# 14_1ST_AP1302_ISP.net
KiCad netlist of a schematic drawn in Altium Designer
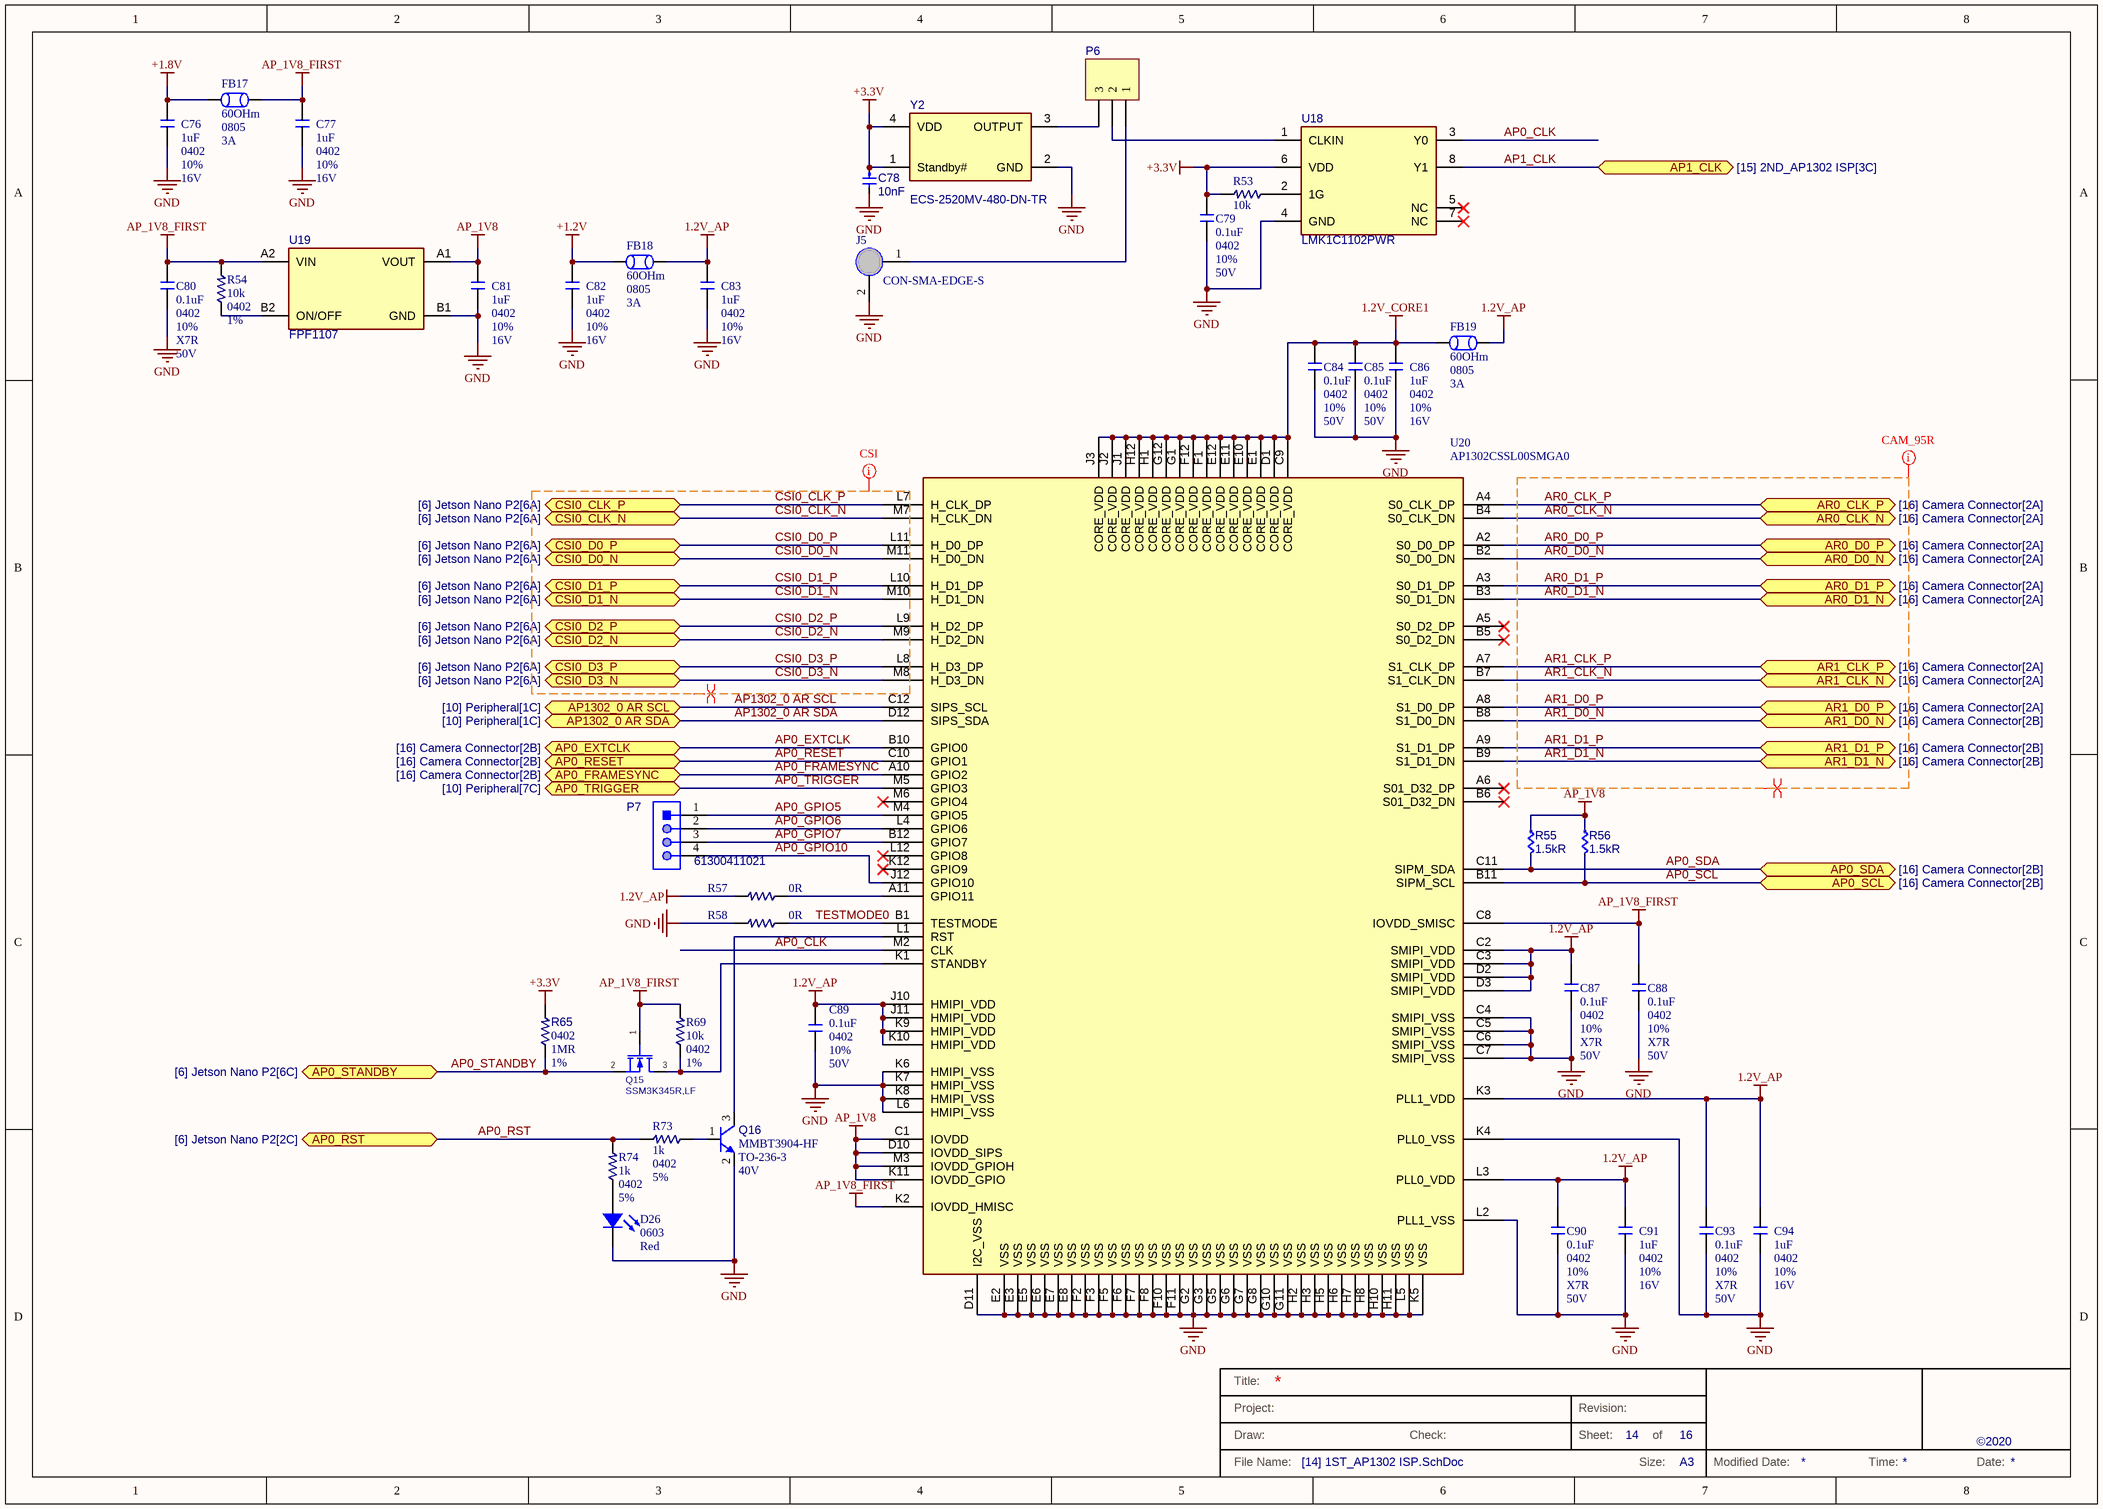
[diagram p0: [14] 1ST_AP1302 ISP.SchDoc]

(export (version "E")
  (design (tool "Eeschema 10.0.6"))
  (components
    (comp (ref "C76")
      (value "1uF")
      (footprint "C0402M")
      (fields
        (field (name "CASE CODE (IMPERIAL)") "0402")
        (field (name "TOLERANCE") "10%")
        (field (name "VOLTAGE") "16V")
      )
      (libsource (lib "CommonLib") (part "CAP_CER"))
    )
    (comp (ref "C77")
      (value "1uF")
      (footprint "C0402M")
      (fields
        (field (name "CASE CODE (IMPERIAL)") "0402")
        (field (name "TOLERANCE") "10%")
        (field (name "VOLTAGE") "16V")
      )
      (libsource (lib "CommonLib") (part "CAP_CER"))
    )
    (comp (ref "C78")
      (value "885012205050")
      (footprint "CAP0402-M")
      (description "CAP CER 10000PF 25V X7R 0402")
      (fields (field (name "TOLERANCE") "10%") (field (name "CAPACITANCE") "10nF"))
      (libsource (lib "Altium Central") (part "=Capacitance"))
    )
    (comp (ref "C79")
      (value "0.1uF")
      (footprint "C0402M")
      (description "CAP CER 0.1UF 50V X7R 0402")
      (fields
        (field (name "MANUFACTURER") "Murata")
        (field (name "MANUFACTURER PART NUMBER") "GRM155R71H104KE14D")
        (field (name "CASE/PACKAGE") "0402")
        (field (name "TOLERANCE") "10%")
        (field (name "VOLTAGE") "50V")
      )
      (libsource (lib "") (part "CAP_CER_1"))
    )
    (comp (ref "C80")
      (value "0.1uF")
      (footprint "C0402M")
      (description "CAP CER 0.1UF 50V X7R 0402")
      (fields
        (field (name "MANUFACTURER") "Murata")
        (field (name "MANUFACTURER PART NUMBER") "GRM155R71H104KE14D")
        (field (name "CASE/PACKAGE") "0402")
        (field (name "TOLERANCE") "10%")
        (field (name "DIELECTRIC") "X7R")
        (field (name "VOLTAGE") "50V")
      )
      (libsource (lib "") (part "CAP_CER_1"))
    )
    (comp (ref "C81")
      (value "1uF")
      (footprint "C0402M")
      (fields
        (field (name "CASE CODE (IMPERIAL)") "0402")
        (field (name "TOLERANCE") "10%")
        (field (name "VOLTAGE") "16V")
      )
      (libsource (lib "CommonLib") (part "CAP_CER"))
    )
    (comp (ref "C82")
      (value "1uF")
      (footprint "C0402M")
      (fields
        (field (name "CASE CODE (IMPERIAL)") "0402")
        (field (name "TOLERANCE") "10%")
        (field (name "VOLTAGE") "16V")
      )
      (libsource (lib "CommonLib") (part "CAP_CER"))
    )
    (comp (ref "C83")
      (value "1uF")
      (footprint "C0402M")
      (fields
        (field (name "CASE CODE (IMPERIAL)") "0402")
        (field (name "TOLERANCE") "10%")
        (field (name "VOLTAGE") "16V")
      )
      (libsource (lib "CommonLib") (part "CAP_CER"))
    )
    (comp (ref "C84")
      (value "0.1uF")
      (footprint "C0402M")
      (description "CAP CER 0.1UF 50V X7R 0402")
      (fields
        (field (name "MANUFACTURER") "Murata")
        (field (name "MANUFACTURER PART NUMBER") "GRM155R71H104KE14D")
        (field (name "CASE/PACKAGE") "0402")
        (field (name "TOLERANCE") "10%")
        (field (name "VOLTAGE") "50V")
      )
      (libsource (lib "") (part "CAP_CER_1"))
    )
    (comp (ref "C85")
      (value "0.1uF")
      (footprint "C0402M")
      (description "CAP CER 0.1UF 50V X7R 0402")
      (fields
        (field (name "MANUFACTURER") "Murata")
        (field (name "MANUFACTURER PART NUMBER") "GRM155R71H104KE14D")
        (field (name "CASE/PACKAGE") "0402")
        (field (name "TOLERANCE") "10%")
        (field (name "VOLTAGE") "50V")
      )
      (libsource (lib "") (part "CAP_CER_1"))
    )
    (comp (ref "C86")
      (value "1uF")
      (footprint "C0402M")
      (fields
        (field (name "CASE CODE (IMPERIAL)") "0402")
        (field (name "TOLERANCE") "10%")
        (field (name "VOLTAGE") "16V")
      )
      (libsource (lib "CommonLib") (part "CAP_CER"))
    )
    (comp (ref "C87")
      (value "0.1uF")
      (footprint "C0402M")
      (description "CAP CER 0.1UF 50V X7R 0402")
      (fields
        (field (name "MANUFACTURER") "Murata")
        (field (name "MANUFACTURER PART NUMBER") "GRM155R71H104KE14D")
        (field (name "CASE/PACKAGE") "0402")
        (field (name "TOLERANCE") "10%")
        (field (name "DIELECTRIC") "X7R")
        (field (name "VOLTAGE") "50V")
      )
      (libsource (lib "") (part "CAP_CER_1"))
    )
    (comp (ref "C88")
      (value "0.1uF")
      (footprint "C0402M")
      (description "CAP CER 0.1UF 50V X7R 0402")
      (fields
        (field (name "MANUFACTURER") "Murata")
        (field (name "MANUFACTURER PART NUMBER") "GRM155R71H104KE14D")
        (field (name "CASE/PACKAGE") "0402")
        (field (name "TOLERANCE") "10%")
        (field (name "DIELECTRIC") "X7R")
        (field (name "VOLTAGE") "50V")
      )
      (libsource (lib "") (part "CAP_CER_1"))
    )
    (comp (ref "C89")
      (value "0.1uF")
      (footprint "C0402M")
      (description "CAP CER 0.1UF 50V X7R 0402")
      (fields
        (field (name "MANUFACTURER") "Murata")
        (field (name "MANUFACTURER PART NUMBER") "GRM155R71H104KE14D")
        (field (name "CASE/PACKAGE") "0402")
        (field (name "TOLERANCE") "10%")
        (field (name "VOLTAGE") "50V")
      )
      (libsource (lib "") (part "CAP_CER_1"))
    )
    (comp (ref "C90")
      (value "0.1uF")
      (footprint "C0402M")
      (description "CAP CER 0.1UF 50V X7R 0402")
      (fields
        (field (name "MANUFACTURER") "Murata")
        (field (name "MANUFACTURER PART NUMBER") "GRM155R71H104KE14D")
        (field (name "CASE/PACKAGE") "0402")
        (field (name "TOLERANCE") "10%")
        (field (name "DIELECTRIC") "X7R")
        (field (name "VOLTAGE") "50V")
      )
      (libsource (lib "") (part "CAP_CER_1"))
    )
    (comp (ref "C91")
      (value "1uF")
      (footprint "C0402M")
      (fields
        (field (name "CASE CODE (IMPERIAL)") "0402")
        (field (name "TOLERANCE") "10%")
        (field (name "VOLTAGE") "16V")
      )
      (libsource (lib "CommonLib") (part "CAP_CER"))
    )
    (comp (ref "C93")
      (value "0.1uF")
      (footprint "C0402M")
      (description "CAP CER 0.1UF 50V X7R 0402")
      (fields
        (field (name "MANUFACTURER") "Murata")
        (field (name "MANUFACTURER PART NUMBER") "GRM155R71H104KE14D")
        (field (name "CASE/PACKAGE") "0402")
        (field (name "TOLERANCE") "10%")
        (field (name "DIELECTRIC") "X7R")
        (field (name "VOLTAGE") "50V")
      )
      (libsource (lib "") (part "CAP_CER_1"))
    )
    (comp (ref "C94")
      (value "1uF")
      (footprint "C0402M")
      (fields
        (field (name "CASE CODE (IMPERIAL)") "0402")
        (field (name "TOLERANCE") "10%")
        (field (name "VOLTAGE") "16V")
      )
      (libsource (lib "CommonLib") (part "CAP_CER"))
    )
    (comp (ref "D26")
      (value "LTST-C190CKT")
      (footprint "LED-0603")
      (description "LED RED CLEAR CHIP SMD")
      (fields (field (name "CASE/PACKAGE") "0603") (field (name "COLOR") "Red"))
      (libsource (lib "CommonLib") (part "Led"))
    )
    (comp (ref "FB17")
      (value "60OHm")
      (footprint "R0805M")
      (fields
        (field (name "CASE CODE (IMPERIAL)") "0805")
        (field (name "TOLERANCE") "25%")
        (field (name "MAX DC CURRENT") "3A")
      )
      (libsource (lib "CommonLib") (part "FB"))
    )
    (comp (ref "FB18")
      (value "60OHm")
      (footprint "R0805M")
      (fields
        (field (name "CASE CODE (IMPERIAL)") "0805")
        (field (name "TOLERANCE") "25%")
        (field (name "MAX DC CURRENT") "3A")
      )
      (libsource (lib "CommonLib") (part "FB"))
    )
    (comp (ref "FB19")
      (value "60OHm")
      (footprint "R0805M")
      (fields
        (field (name "CASE CODE (IMPERIAL)") "0805")
        (field (name "TOLERANCE") "25%")
        (field (name "MAX DC CURRENT") "3A")
      )
      (libsource (lib "CommonLib") (part "FB"))
    )
    (comp (ref "J5")
      (value "CON-SMA-EDGE-S")
      (footprint "CON-SMA-EDGE-S")
      (description "Sma Female Connector, Pcb Edge Mount Rohs Compliant: Yes")
      (libsource (lib "CommonLib") (part "AntenaIPX"))
    )
    (comp (ref "P6")
      (value "Header 3")
      (footprint "HDR1X3")
      (description "Header, 3-Pin")
      (fields (field (name "PUBLISHER") "Altium Limited"))
      (libsource (lib "3DAS_4Camera") (part "Header 3"))
    )
    (comp (ref "P7")
      (value "61300411021")
      (footprint "61300411021")
      (description "CONN HEADER VERT 4POS 2.54MM")
      (fields (field (name "MANUFACTURER") "Würth Elektronik GmbH"))
      (libsource (lib "3DAS_4Camera") (part "WE-CN-1P-M-R4"))
    )
    (comp (ref "Q15")
      (value "SSM3K345R,LF")
      (footprint "SSM3K345R,LF-Footprint-1")
      (description "MOSFET N-CHANNEL 20V 4A SOT23F")
      (libsource (lib "Altium Central") (part "SSM3K345R,LF"))
    )
    (comp (ref "Q16")
      (value "NPN")
      (footprint "SOT55P160X90-3N")
      (description "TRANS NPN 40V 0.2A SOT523")
      (fields
        (field (name "MANUFACTURER PART NUMBER 1") "MMBT3904-HF")
        (field (name "CASE/PACKAGE") "TO-236-3")
        (field (name "COLLECTOR EMITTER BREAKDOWN VOLTAGE") "40V")
      )
      (libsource (lib "3DAS_4Camera") (part "NPN"))
    )
    (comp (ref "R53")
      (value "10k")
      (footprint "R0402M")
      (description "RES SMD 10K OHM 1% 1/16W 0402")
      (fields
        (field (name "MANUFACTURER") "Yageo")
        (field (name "MANUFACTURER PART NUMBER") "RC0402FR-0710KL")
      )
      (libsource (lib "CommonLib") (part "RES_SMD"))
    )
    (comp (ref "R54")
      (value "10k")
      (footprint "R0402M")
      (description "RES SMD 10K OHM 1% 1/16W 0402")
      (fields
        (field (name "MANUFACTURER") "Yageo")
        (field (name "MANUFACTURER PART NUMBER") "RC0402FR-0710KL")
        (field (name "CASE CODE (IMPERIAL)") "0402")
        (field (name "TOLERANCE") "1%")
      )
      (libsource (lib "CommonLib") (part "RES_SMD"))
    )
    (comp (ref "R55")
      (value "ERJ-2RKF1501X")
      (footprint "RES0402")
      (description "RES SMD 1.5K OHM 1% 1/10W 0402")
      (fields (field (name "RESISTANCE") "1.5kR") (field (name "TOLERANCE") "1%"))
      (libsource (lib "Altium Central") (part "=Resistance"))
    )
    (comp (ref "R56")
      (value "ERJ-2RKF1501X")
      (footprint "RES0402")
      (description "RES SMD 1.5K OHM 1% 1/10W 0402")
      (fields (field (name "RESISTANCE") "1.5kR") (field (name "TOLERANCE") "1%"))
      (libsource (lib "Altium Central") (part "=Resistance"))
    )
    (comp (ref "R57")
      (value "RC0402FR-070RL")
      (footprint "R0402M")
      (description "RC Series 0402 0.063 W 0 Ohm Jumper Surface Mount Thick Film Chip Resistor")
      (fields (field (name "RESISTANCE") "0R") (field (name "TOLERANCE") "1%"))
      (libsource (lib "CommonLib") (part "RES_SMD"))
    )
    (comp (ref "R58")
      (value "RC0402FR-070RL")
      (footprint "R0402M")
      (description "RC Series 0402 0.063 W 0 Ohm Jumper Surface Mount Thick Film Chip Resistor")
      (fields (field (name "RESISTANCE") "0R") (field (name "TOLERANCE") "1%"))
      (libsource (lib "CommonLib") (part "RES_SMD"))
    )
    (comp (ref "R65")
      (value "1M")
      (footprint "R0402M")
      (description "RES SMD 1M OHM 1% 1/16W 0402")
      (fields
        (field (name "MANUFACTURER") "Yageo")
        (field (name "MANUFACTURER PART NUMBER") "RC0402FR-071ML")
        (field (name "CASE CODE (IMPERIAL)") "0402")
        (field (name "RESISTANCE") "1MR")
        (field (name "TOLERANCE") "1%")
      )
      (libsource (lib "3DAS_4Camera") (part "RES_SMD_17"))
    )
    (comp (ref "R69")
      (value "10k")
      (footprint "R0402M")
      (description "RES SMD 10K OHM 1% 1/16W 0402")
      (fields
        (field (name "MANUFACTURER") "Yageo")
        (field (name "MANUFACTURER PART NUMBER") "RC0402FR-0710KL")
        (field (name "CASE CODE (IMPERIAL)") "0402")
        (field (name "TOLERANCE") "1%")
      )
      (libsource (lib "CommonLib") (part "RES_SMD"))
    )
    (comp (ref "R73")
      (value "1k")
      (footprint "R0402M")
      (description "RES SMD 1K OHM 5% 1/16W 0402")
      (fields
        (field (name "MANUFACTURER") "Yageo")
        (field (name "MANUFACTURER PART NUMBER") "RC0402JR-071KL")
        (field (name "CASE CODE (IMPERIAL)") "0402")
        (field (name "TOLERANCE") "5%")
      )
      (libsource (lib "CommonLib") (part "RES_SMD"))
    )
    (comp (ref "R74")
      (value "1k")
      (footprint "R0402M")
      (description "RES SMD 1K OHM 5% 1/16W 0402")
      (fields
        (field (name "MANUFACTURER") "Yageo")
        (field (name "MANUFACTURER PART NUMBER") "RC0402JR-071KL")
        (field (name "CASE CODE (IMPERIAL)") "0402")
        (field (name "TOLERANCE") "5%")
      )
      (libsource (lib "CommonLib") (part "RES_SMD"))
    )
    (comp (ref "U18")
      (value "LMK1C1102PWR")
      (footprint "LMK1C1102PWR")
      (description "Clock Buffer LVCMOS 1: 4 1.8V/2.5V/3.3V 8-Pin TSSOP T/R")
      (fields (field (name "MANUFACTURER") "Texas Instruments"))
      (libsource (lib "3DAS_4Camera") (part "LMK1C1102PWR"))
    )
    (comp (ref "U19")
      (value "FPF1107")
      (footprint "FPF1107")
      (description "IC PWR SWITCH P-CHAN 1:1 4WLCSP")
      (fields (field (name "MANUFACTURER") "ON Semiconductor / Fairchild") (field (name "VOLTAGE") "4V"))
      (libsource (lib "3DAS_4Camera") (part "FPF1107"))
    )
    (comp (ref "U20")
      (value "AP1302CSSL00SMGA0")
      (footprint "AP1302CSSL00SMGA0")
      (description "IMAGE SENSOR 13 MP CO-PROCESSOR")
      (fields
        (field (name "MANUFACTURER") "ON Semiconductor")
        (field (name "MANUFACTURER PART NUMBER") "AP1302CSSL00SMGA0-DR")
      )
      (libsource (lib "3DAS_4Camera") (part "AP1302"))
    )
    (comp (ref "Y2")
      (value "ECS-2520MV-480-DN-TR")
      (footprint "ECS-2520MV-480-DN-TR")
      (description "XTAL OSC XO 48.0000MHZ CMOS SMD")
      (fields
        (field (name "MANUFACTURER") "ECS International")
        (field (name "MANUFACTURER PART NUMBER") "ECS-2520MV-480-DN-TR")
      )
      (libsource (lib "3DAS_4Camera") (part "ASFLMB-48.000MHZ-LR-T"))
    )
  )
  (nets
    (net (code "1") (name "+1.2V") (class "Default")
      (node (ref "C82") (pin "1") (pinfunction "1_1") (pintype "passive"))
      (node (ref "FB18") (pin "2") (pinfunction "2_2") (pintype "passive"))
    )
    (net (code "2") (name "+1.8V") (class "Default")
      (node (ref "C76") (pin "1") (pinfunction "1_1") (pintype "passive"))
      (node (ref "FB17") (pin "2") (pinfunction "2_2") (pintype "passive"))
    )
    (net (code "3") (name "+3.3V") (class "Default")
      (node (ref "C78") (pin "1") (pinfunction "1_1") (pintype "passive"))
      (node (ref "C79") (pin "1") (pinfunction "1_1") (pintype "passive"))
      (node (ref "R53") (pin "1") (pinfunction "1_1") (pintype "passive"))
      (node (ref "R65") (pin "1") (pinfunction "1_1") (pintype "passive"))
      (node (ref "U18") (pin "6") (pinfunction "VDD_6") (pintype "passive"))
      (node (ref "Y2") (pin "1") (pinfunction "Standby#_1") (pintype "passive"))
      (node (ref "Y2") (pin "4") (pinfunction "VDD_4") (pintype "passive"))
    )
    (net (code "4") (name "/AP0_CLK") (class "Default")
      (node (ref "U18") (pin "3") (pinfunction "Y0_3") (pintype "passive"))
      (node (ref "U20") (pin "M2") (pinfunction "CLK_M2") (pintype "passive"))
    )
    (net (code "5") (name "/AP0_EXTCLK") (class "Default")
      (node (ref "U20") (pin "B10") (pinfunction "GPIO0_B10") (pintype "passive"))
    )
    (net (code "6") (name "/AP0_FRAMESYNC") (class "Default")
      (node (ref "U20") (pin "A10") (pinfunction "GPIO2_A10") (pintype "passive"))
    )
    (net (code "7") (name "/AP0_GPIO5") (class "Default")
      (node (ref "P7") (pin "1") (pinfunction "1_1") (pintype "passive"))
      (node (ref "U20") (pin "M4") (pinfunction "GPIO5_M4") (pintype "passive"))
    )
    (net (code "8") (name "/AP0_GPIO6") (class "Default")
      (node (ref "P7") (pin "2") (pinfunction "2_2") (pintype "passive"))
      (node (ref "U20") (pin "L4") (pinfunction "GPIO6_L4") (pintype "passive"))
    )
    (net (code "9") (name "/AP0_GPIO7") (class "Default")
      (node (ref "P7") (pin "3") (pinfunction "3_3") (pintype "passive"))
      (node (ref "U20") (pin "B12") (pinfunction "GPIO7_B12") (pintype "passive"))
    )
    (net (code "10") (name "/AP0_GPIO10") (class "Default")
      (node (ref "P7") (pin "4") (pinfunction "4_4") (pintype "passive"))
      (node (ref "U20") (pin "J12") (pinfunction "GPIO10_J12") (pintype "passive"))
    )
    (net (code "11") (name "/AP0_RESET") (class "Default")
      (node (ref "U20") (pin "C10") (pinfunction "GPIO1_C10") (pintype "passive"))
    )
    (net (code "12") (name "/AP0_RST") (class "Default")
      (node (ref "R73") (pin "1") (pinfunction "1_1") (pintype "passive"))
      (node (ref "R74") (pin "1") (pinfunction "1_1") (pintype "passive"))
    )
    (net (code "13") (name "/AP0_SCL") (class "Default")
      (node (ref "R56") (pin "2") (pinfunction "2_2") (pintype "passive"))
      (node (ref "U20") (pin "B11") (pinfunction "SIPM_SCL_B11") (pintype "passive"))
    )
    (net (code "14") (name "/AP0_SDA") (class "Default")
      (node (ref "R55") (pin "2") (pinfunction "2_2") (pintype "passive"))
      (node (ref "U20") (pin "C11") (pinfunction "SIPM_SDA_C11") (pintype "passive"))
    )
    (net (code "15") (name "/AP0_STANDBY") (class "Default")
      (node (ref "Q15") (pin "2") (pinfunction "S_2") (pintype "passive"))
      (node (ref "R65") (pin "2") (pinfunction "2_2") (pintype "passive"))
    )
    (net (code "16") (name "/AP0_TRIGGER") (class "Default")
      (node (ref "U20") (pin "M5") (pinfunction "GPIO3_M5") (pintype "passive"))
    )
    (net (code "17") (name "/AP1_CLK") (class "Default")
      (node (ref "U18") (pin "8") (pinfunction "Y1_8") (pintype "passive"))
    )
    (net (code "18") (name "/AP1302_0 AR SCL") (class "Default")
      (node (ref "U20") (pin "C12") (pinfunction "SIPS_SCL_C12") (pintype "passive"))
    )
    (net (code "19") (name "/AP1302_0 AR SDA") (class "Default")
      (node (ref "U20") (pin "D12") (pinfunction "SIPS_SDA_D12") (pintype "passive"))
    )
    (net (code "20") (name "/AR0_CLK_N") (class "Default")
      (node (ref "U20") (pin "B4") (pinfunction "S0_CLK_DN_B4") (pintype "passive"))
    )
    (net (code "21") (name "/AR0_CLK_P") (class "Default")
      (node (ref "U20") (pin "A4") (pinfunction "S0_CLK_DP_A4") (pintype "passive"))
    )
    (net (code "22") (name "/AR0_D0_N") (class "Default")
      (node (ref "U20") (pin "B2") (pinfunction "S0_D0_DN_B2") (pintype "passive"))
    )
    (net (code "23") (name "/AR0_D0_P") (class "Default")
      (node (ref "U20") (pin "A2") (pinfunction "S0_D0_DP_A2") (pintype "passive"))
    )
    (net (code "24") (name "/AR0_D1_N") (class "Default")
      (node (ref "U20") (pin "B3") (pinfunction "S0_D1_DN_B3") (pintype "passive"))
    )
    (net (code "25") (name "/AR0_D1_P") (class "Default")
      (node (ref "U20") (pin "A3") (pinfunction "S0_D1_DP_A3") (pintype "passive"))
    )
    (net (code "26") (name "/AR1_CLK_N") (class "Default")
      (node (ref "U20") (pin "B7") (pinfunction "S1_CLK_DN_B7") (pintype "passive"))
    )
    (net (code "27") (name "/AR1_CLK_P") (class "Default")
      (node (ref "U20") (pin "A7") (pinfunction "S1_CLK_DP_A7") (pintype "passive"))
    )
    (net (code "28") (name "/AR1_D0_N") (class "Default")
      (node (ref "U20") (pin "B8") (pinfunction "S1_D0_DN_B8") (pintype "passive"))
    )
    (net (code "29") (name "/AR1_D0_P") (class "Default")
      (node (ref "U20") (pin "A8") (pinfunction "S1_D0_DP_A8") (pintype "passive"))
    )
    (net (code "30") (name "/AR1_D1_N") (class "Default")
      (node (ref "U20") (pin "B9") (pinfunction "S1_D1_DN_B9") (pintype "passive"))
    )
    (net (code "31") (name "/AR1_D1_P") (class "Default")
      (node (ref "U20") (pin "A9") (pinfunction "S1_D1_DP_A9") (pintype "passive"))
    )
    (net (code "32") (name "/CSI0_CLK_N") (class "Default")
      (node (ref "U20") (pin "M7") (pinfunction "H_CLK_DN_M7") (pintype "passive"))
    )
    (net (code "33") (name "/CSI0_CLK_P") (class "Default")
      (node (ref "U20") (pin "L7") (pinfunction "H_CLK_DP_L7") (pintype "passive"))
    )
    (net (code "34") (name "/CSI0_D0_N") (class "Default")
      (node (ref "U20") (pin "M11") (pinfunction "H_D0_DN_M11") (pintype "passive"))
    )
    (net (code "35") (name "/CSI0_D0_P") (class "Default")
      (node (ref "U20") (pin "L11") (pinfunction "H_D0_DP_L11") (pintype "passive"))
    )
    (net (code "36") (name "/CSI0_D1_N") (class "Default")
      (node (ref "U20") (pin "M10") (pinfunction "H_D1_DN_M10") (pintype "passive"))
    )
    (net (code "37") (name "/CSI0_D1_P") (class "Default")
      (node (ref "U20") (pin "L10") (pinfunction "H_D1_DP_L10") (pintype "passive"))
    )
    (net (code "38") (name "/CSI0_D2_N") (class "Default")
      (node (ref "U20") (pin "M9") (pinfunction "H_D2_DN_M9") (pintype "passive"))
    )
    (net (code "39") (name "/CSI0_D2_P") (class "Default")
      (node (ref "U20") (pin "L9") (pinfunction "H_D2_DP_L9") (pintype "passive"))
    )
    (net (code "40") (name "/CSI0_D3_N") (class "Default")
      (node (ref "U20") (pin "M8") (pinfunction "H_D3_DN_M8") (pintype "passive"))
    )
    (net (code "41") (name "/CSI0_D3_P") (class "Default")
      (node (ref "U20") (pin "L8") (pinfunction "H_D3_DP_L8") (pintype "passive"))
    )
    (net (code "42") (name "/TESTMODE0") (class "Default")
      (node (ref "R58") (pin "2") (pinfunction "2_2") (pintype "passive"))
      (node (ref "U20") (pin "B1") (pinfunction "TESTMODE_B1") (pintype "passive"))
    )
    (net (code "43") (name "1.2V_AP") (class "Default")
      (node (ref "C83") (pin "1") (pinfunction "1_1") (pintype "passive"))
      (node (ref "C87") (pin "1") (pinfunction "1_1") (pintype "passive"))
      (node (ref "C89") (pin "1") (pinfunction "1_1") (pintype "passive"))
      (node (ref "C90") (pin "1") (pinfunction "1_1") (pintype "passive"))
      (node (ref "C91") (pin "1") (pinfunction "1_1") (pintype "passive"))
      (node (ref "C93") (pin "1") (pinfunction "1_1") (pintype "passive"))
      (node (ref "C94") (pin "1") (pinfunction "1_1") (pintype "passive"))
      (node (ref "FB18") (pin "1") (pinfunction "1_1") (pintype "passive"))
      (node (ref "FB19") (pin "1") (pinfunction "1_1") (pintype "passive"))
      (node (ref "R57") (pin "1") (pinfunction "1_1") (pintype "passive"))
      (node (ref "U20") (pin "C2") (pinfunction "SMIPI_VDD_C2") (pintype "passive"))
      (node (ref "U20") (pin "C3") (pinfunction "SMIPI_VDD_C3") (pintype "passive"))
      (node (ref "U20") (pin "D2") (pinfunction "SMIPI_VDD_D2") (pintype "passive"))
      (node (ref "U20") (pin "D3") (pinfunction "SMIPI_VDD_D3") (pintype "passive"))
      (node (ref "U20") (pin "J10") (pinfunction "HMIPI_VDD_J10") (pintype "passive"))
      (node (ref "U20") (pin "J11") (pinfunction "HMIPI_VDD_J11") (pintype "passive"))
      (node (ref "U20") (pin "K10") (pinfunction "HMIPI_VDD_K10") (pintype "passive"))
      (node (ref "U20") (pin "K3") (pinfunction "PLL1_VDD_K3") (pintype "passive"))
      (node (ref "U20") (pin "K9") (pinfunction "HMIPI_VDD_K9") (pintype "passive"))
      (node (ref "U20") (pin "L3") (pinfunction "PLL0_VDD_L3") (pintype "passive"))
    )
    (net (code "44") (name "1.2V_CORE1") (class "Default")
      (node (ref "C84") (pin "1") (pinfunction "1_1") (pintype "passive"))
      (node (ref "C85") (pin "1") (pinfunction "1_1") (pintype "passive"))
      (node (ref "C86") (pin "1") (pinfunction "1_1") (pintype "passive"))
      (node (ref "FB19") (pin "2") (pinfunction "2_2") (pintype "passive"))
      (node (ref "U20") (pin "C9") (pinfunction "CORE_VDD_C9") (pintype "passive"))
      (node (ref "U20") (pin "D1") (pinfunction "CORE_VDD_D1") (pintype "passive"))
      (node (ref "U20") (pin "E1") (pinfunction "CORE_VDD_E1") (pintype "passive"))
      (node (ref "U20") (pin "E10") (pinfunction "CORE_VDD_E10") (pintype "passive"))
      (node (ref "U20") (pin "E11") (pinfunction "CORE_VDD_E11") (pintype "passive"))
      (node (ref "U20") (pin "E12") (pinfunction "CORE_VDD_E12") (pintype "passive"))
      (node (ref "U20") (pin "F1") (pinfunction "CORE_VDD_F1") (pintype "passive"))
      (node (ref "U20") (pin "F12") (pinfunction "CORE_VDD_F12") (pintype "passive"))
      (node (ref "U20") (pin "G1") (pinfunction "CORE_VDD_G1") (pintype "passive"))
      (node (ref "U20") (pin "G12") (pinfunction "CORE_VDD_G12") (pintype "passive"))
      (node (ref "U20") (pin "H1") (pinfunction "CORE_VDD_H1") (pintype "passive"))
      (node (ref "U20") (pin "H12") (pinfunction "CORE_VDD_H12") (pintype "passive"))
      (node (ref "U20") (pin "J1") (pinfunction "CORE_VDD_J1") (pintype "passive"))
      (node (ref "U20") (pin "J2") (pinfunction "CORE_VDD_J2") (pintype "passive"))
      (node (ref "U20") (pin "J3") (pinfunction "CORE_VDD_J3") (pintype "passive"))
    )
    (net (code "45") (name "AP_1V8") (class "Default")
      (node (ref "C81") (pin "1") (pinfunction "1_1") (pintype "passive"))
      (node (ref "R55") (pin "1") (pinfunction "1_1") (pintype "passive"))
      (node (ref "R56") (pin "1") (pinfunction "1_1") (pintype "passive"))
      (node (ref "U19") (pin "A1") (pinfunction "VOUT_A1") (pintype "passive"))
      (node (ref "U20") (pin "C1") (pinfunction "IOVDD_C1") (pintype "passive"))
      (node (ref "U20") (pin "D10") (pinfunction "IOVDD_SIPS_D10") (pintype "passive"))
      (node (ref "U20") (pin "K11") (pinfunction "IOVDD_GPIO_K11") (pintype "passive"))
      (node (ref "U20") (pin "M3") (pinfunction "IOVDD_GPIOH_M3") (pintype "passive"))
    )
    (net (code "46") (name "AP_1V8_FIRST") (class "Default")
      (node (ref "C77") (pin "1") (pinfunction "1_1") (pintype "passive"))
      (node (ref "C80") (pin "1") (pinfunction "1_1") (pintype "passive"))
      (node (ref "C88") (pin "1") (pinfunction "1_1") (pintype "passive"))
      (node (ref "FB17") (pin "1") (pinfunction "1_1") (pintype "passive"))
      (node (ref "Q15") (pin "1") (pinfunction "G_1") (pintype "passive"))
      (node (ref "R54") (pin "1") (pinfunction "1_1") (pintype "passive"))
      (node (ref "R69") (pin "1") (pinfunction "1_1") (pintype "passive"))
      (node (ref "U19") (pin "A2") (pinfunction "VIN_A2") (pintype "passive"))
      (node (ref "U20") (pin "C8") (pinfunction "IOVDD_SMISC_C8") (pintype "passive"))
      (node (ref "U20") (pin "K2") (pinfunction "IOVDD_HMISC_K2") (pintype "passive"))
    )
    (net (code "47") (name "GND") (class "Default")
      (node (ref "C76") (pin "2") (pinfunction "2_2") (pintype "passive"))
      (node (ref "C77") (pin "2") (pinfunction "2_2") (pintype "passive"))
      (node (ref "C78") (pin "2") (pinfunction "2_2") (pintype "passive"))
      (node (ref "C79") (pin "2") (pinfunction "2_2") (pintype "passive"))
      (node (ref "C80") (pin "2") (pinfunction "2_2") (pintype "passive"))
      (node (ref "C81") (pin "2") (pinfunction "2_2") (pintype "passive"))
      (node (ref "C82") (pin "2") (pinfunction "2_2") (pintype "passive"))
      (node (ref "C83") (pin "2") (pinfunction "2_2") (pintype "passive"))
      (node (ref "C84") (pin "2") (pinfunction "2_2") (pintype "passive"))
      (node (ref "C85") (pin "2") (pinfunction "2_2") (pintype "passive"))
      (node (ref "C86") (pin "2") (pinfunction "2_2") (pintype "passive"))
      (node (ref "C87") (pin "2") (pinfunction "2_2") (pintype "passive"))
      (node (ref "C88") (pin "2") (pinfunction "2_2") (pintype "passive"))
      (node (ref "C89") (pin "2") (pinfunction "2_2") (pintype "passive"))
      (node (ref "C90") (pin "2") (pinfunction "2_2") (pintype "passive"))
      (node (ref "C91") (pin "2") (pinfunction "2_2") (pintype "passive"))
      (node (ref "C93") (pin "2") (pinfunction "2_2") (pintype "passive"))
      (node (ref "C94") (pin "2") (pinfunction "2_2") (pintype "passive"))
      (node (ref "D26") (pin "2") (pinfunction "K_2") (pintype "passive"))
      (node (ref "J5") (pin "2") (pinfunction "GND_2") (pintype "passive"))
      (node (ref "Q16") (pin "2") (pinfunction "E_2") (pintype "passive"))
      (node (ref "R58") (pin "1") (pinfunction "1_1") (pintype "passive"))
      (node (ref "U18") (pin "4") (pinfunction "GND_4") (pintype "passive"))
      (node (ref "U19") (pin "B1") (pinfunction "GND_B1") (pintype "passive"))
      (node (ref "U20") (pin "C4") (pinfunction "SMIPI_VSS_C4") (pintype "passive"))
      (node (ref "U20") (pin "C5") (pinfunction "SMIPI_VSS_C5") (pintype "passive"))
      (node (ref "U20") (pin "C6") (pinfunction "SMIPI_VSS_C6") (pintype "passive"))
      (node (ref "U20") (pin "C7") (pinfunction "SMIPI_VSS_C7") (pintype "passive"))
      (node (ref "U20") (pin "D11") (pinfunction "I2C_VSS_D11") (pintype "passive"))
      (node (ref "U20") (pin "E2") (pinfunction "VSS_E2") (pintype "passive"))
      (node (ref "U20") (pin "E3") (pinfunction "VSS_E3") (pintype "passive"))
      (node (ref "U20") (pin "E5") (pinfunction "VSS_E5") (pintype "passive"))
      (node (ref "U20") (pin "E6") (pinfunction "VSS_E6") (pintype "passive"))
      (node (ref "U20") (pin "E7") (pinfunction "VSS_E7") (pintype "passive"))
      (node (ref "U20") (pin "E8") (pinfunction "VSS_E8") (pintype "passive"))
      (node (ref "U20") (pin "F10") (pinfunction "VSS_F10") (pintype "passive"))
      (node (ref "U20") (pin "F11") (pinfunction "VSS_F11") (pintype "passive"))
      (node (ref "U20") (pin "F2") (pinfunction "VSS_F2") (pintype "passive"))
      (node (ref "U20") (pin "F3") (pinfunction "VSS_F3") (pintype "passive"))
      (node (ref "U20") (pin "F5") (pinfunction "VSS_F5") (pintype "passive"))
      (node (ref "U20") (pin "F6") (pinfunction "VSS_F6") (pintype "passive"))
      (node (ref "U20") (pin "F7") (pinfunction "VSS_F7") (pintype "passive"))
      (node (ref "U20") (pin "F8") (pinfunction "VSS_F8") (pintype "passive"))
      (node (ref "U20") (pin "G10") (pinfunction "VSS_G10") (pintype "passive"))
      (node (ref "U20") (pin "G11") (pinfunction "VSS_G11") (pintype "passive"))
      (node (ref "U20") (pin "G2") (pinfunction "VSS_G2") (pintype "passive"))
      (node (ref "U20") (pin "G3") (pinfunction "VSS_G3") (pintype "passive"))
      (node (ref "U20") (pin "G5") (pinfunction "VSS_G5") (pintype "passive"))
      (node (ref "U20") (pin "G6") (pinfunction "VSS_G6") (pintype "passive"))
      (node (ref "U20") (pin "G7") (pinfunction "VSS_G7") (pintype "passive"))
      (node (ref "U20") (pin "G8") (pinfunction "VSS_G8") (pintype "passive"))
      (node (ref "U20") (pin "H10") (pinfunction "VSS_H10") (pintype "passive"))
      (node (ref "U20") (pin "H11") (pinfunction "VSS_H11") (pintype "passive"))
      (node (ref "U20") (pin "H2") (pinfunction "VSS_H2") (pintype "passive"))
      (node (ref "U20") (pin "H3") (pinfunction "VSS_H3") (pintype "passive"))
      (node (ref "U20") (pin "H5") (pinfunction "VSS_H5") (pintype "passive"))
      (node (ref "U20") (pin "H6") (pinfunction "VSS_H6") (pintype "passive"))
      (node (ref "U20") (pin "H7") (pinfunction "VSS_H7") (pintype "passive"))
      (node (ref "U20") (pin "H8") (pinfunction "VSS_H8") (pintype "passive"))
      (node (ref "U20") (pin "K4") (pinfunction "PLL0_VSS_K4") (pintype "passive"))
      (node (ref "U20") (pin "K5") (pinfunction "VSS_K5") (pintype "passive"))
      (node (ref "U20") (pin "K6") (pinfunction "HMIPI_VSS_K6") (pintype "passive"))
      (node (ref "U20") (pin "K7") (pinfunction "HMIPI_VSS_K7") (pintype "passive"))
      (node (ref "U20") (pin "K8") (pinfunction "HMIPI_VSS_K8") (pintype "passive"))
      (node (ref "U20") (pin "L2") (pinfunction "PLL1_VSS_L2") (pintype "passive"))
      (node (ref "U20") (pin "L5") (pinfunction "VSS_L5") (pintype "passive"))
      (node (ref "U20") (pin "L6") (pinfunction "HMIPI_VSS_L6") (pintype "passive"))
      (node (ref "Y2") (pin "2") (pinfunction "GND_2") (pintype "passive"))
    )
    (net (code "48") (name "Net-(D26-A)") (class "Default")
      (node (ref "D26") (pin "1") (pinfunction "A_1") (pintype "passive"))
      (node (ref "R74") (pin "2") (pinfunction "2_2") (pintype "passive"))
    )
    (net (code "49") (name "Net-(J5-SIG)") (class "Default")
      (node (ref "J5") (pin "1") (pinfunction "SIG_1") (pintype "passive"))
      (node (ref "P6") (pin "1") (pinfunction "1_1") (pintype "passive"))
    )
    (net (code "50") (name "Net-(Q15-D)") (class "Default")
      (node (ref "Q15") (pin "3") (pinfunction "D_3") (pintype "passive"))
      (node (ref "R69") (pin "2") (pinfunction "2_2") (pintype "passive"))
      (node (ref "U20") (pin "K1") (pinfunction "STANDBY_K1") (pintype "passive"))
    )
    (net (code "51") (name "Net-(Q16-B)") (class "Default")
      (node (ref "Q16") (pin "1") (pinfunction "B_1") (pintype "passive"))
      (node (ref "R73") (pin "2") (pinfunction "2_2") (pintype "passive"))
    )
    (net (code "52") (name "Net-(Q16-C)") (class "Default")
      (node (ref "Q16") (pin "3") (pinfunction "C_3") (pintype "passive"))
      (node (ref "U20") (pin "L1") (pinfunction "RST_L1") (pintype "passive"))
    )
    (net (code "53") (name "Net-(U18-1G)") (class "Default")
      (node (ref "R53") (pin "2") (pinfunction "2_2") (pintype "passive"))
      (node (ref "U18") (pin "2") (pinfunction "1G_2") (pintype "passive"))
    )
    (net (code "54") (name "Net-(U18-CLKIN)") (class "Default")
      (node (ref "P6") (pin "2") (pinfunction "2_2") (pintype "passive"))
      (node (ref "U18") (pin "1") (pinfunction "CLKIN_1") (pintype "passive"))
    )
    (net (code "55") (name "Net-(U19-ON{slash}OFF)") (class "Default")
      (node (ref "R54") (pin "2") (pinfunction "2_2") (pintype "passive"))
      (node (ref "U19") (pin "B2") (pinfunction "ON/OFF_B2") (pintype "passive"))
    )
    (net (code "56") (name "Net-(U20-GPIO11)") (class "Default")
      (node (ref "R57") (pin "2") (pinfunction "2_2") (pintype "passive"))
      (node (ref "U20") (pin "A11") (pinfunction "GPIO11_A11") (pintype "passive"))
    )
    (net (code "57") (name "Net-(Y2-OUTPUT)") (class "Default")
      (node (ref "P6") (pin "3") (pinfunction "3_3") (pintype "passive"))
      (node (ref "Y2") (pin "3") (pinfunction "OUTPUT_3") (pintype "passive"))
    )
    (net (code "58") (name "unconnected-(U18-NC-Pad5)") (class "Default")
      (node (ref "U18") (pin "5") (pinfunction "NC_5") (pintype "passive+no_connect"))
    )
    (net (code "59") (name "unconnected-(U18-NC-Pad7)") (class "Default")
      (node (ref "U18") (pin "7") (pinfunction "NC_7") (pintype "passive+no_connect"))
    )
    (net (code "60") (name "unconnected-(U20-GPIO4-PadM6)") (class "Default")
      (node (ref "U20") (pin "M6") (pinfunction "GPIO4_M6") (pintype "passive+no_connect"))
    )
    (net (code "61") (name "unconnected-(U20-GPIO8-PadL12)") (class "Default")
      (node (ref "U20") (pin "L12") (pinfunction "GPIO8_L12") (pintype "passive+no_connect"))
    )
    (net (code "62") (name "unconnected-(U20-GPIO9-PadK12)") (class "Default")
      (node (ref "U20") (pin "K12") (pinfunction "GPIO9_K12") (pintype "passive+no_connect"))
    )
    (net (code "63") (name "unconnected-(U20-S0_D2_DN-PadB5)") (class "Default")
      (node (ref "U20") (pin "B5") (pinfunction "S0_D2_DN_B5") (pintype "passive+no_connect"))
    )
    (net (code "64") (name "unconnected-(U20-S0_D2_DP-PadA5)") (class "Default")
      (node (ref "U20") (pin "A5") (pinfunction "S0_D2_DP_A5") (pintype "passive+no_connect"))
    )
    (net (code "65") (name "unconnected-(U20-S01_D32_DN-PadB6)") (class "Default")
      (node (ref "U20") (pin "B6") (pinfunction "S01_D32_DN_B6") (pintype "passive+no_connect"))
    )
    (net (code "66") (name "unconnected-(U20-S01_D32_DP-PadA6)") (class "Default")
      (node (ref "U20") (pin "A6") (pinfunction "S01_D32_DP_A6") (pintype "passive+no_connect"))
    )
  )
)
